# SCH__OldDriver.net
KiCad netlist of a schematic drawn in Altium Designer
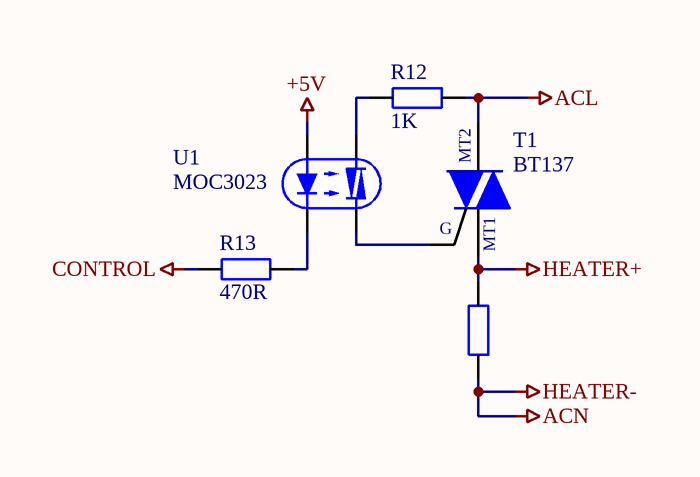
[diagram p0: [SCH]_OldDriver.SchDoc]

(export (version "E")
  (design (tool "Eeschema 10.0.6"))
  (components
    (comp (ref "R12")
      (value "1K")
      (footprint "Res1/4W")
      (description "Resistor 1/4W")
      (libsource (lib "Library") (part "Res 1/4W"))
    )
    (comp (ref "R13")
      (value "470R")
      (footprint "Res1/4W")
      (description "Resistor 1/4W")
      (libsource (lib "Library") (part "Res 1/4W"))
    )
    (comp (ref "SENSOR2")
      (value "5R")
      (footprint "Res1/4W")
      (description "Resistor 1/4W")
      (libsource (lib "Library") (part "Res 1/4W"))
    )
    (comp (ref "T1")
      (value "BT137")
      (footprint "TO220H2")
      (description "Triacs - 8A")
      (libsource (lib "Library") (part "BT137"))
    )
    (comp (ref "U1")
      (value "MOC3023")
      (footprint "DIL6-300b")
      (libsource (lib "Opto Coupler") (part "MOC3023"))
    )
  )
  (nets
    (net (code "1") (name "+5V") (class "Default")
      (node (ref "U1") (pin "1") (pinfunction "A_1") (pintype "passive"))
    )
    (net (code "2") (name "ACL") (class "Default")
      (node (ref "R12") (pin "2") (pinfunction "2_2") (pintype "passive"))
      (node (ref "T1") (pin "2") (pinfunction "MT2_2") (pintype "passive"))
    )
    (net (code "3") (name "ACN") (class "Default")
      (node (ref "SENSOR2") (pin "1") (pinfunction "1_1") (pintype "passive"))
    )
    (net (code "4") (name "CONTROL") (class "Default")
      (node (ref "R13") (pin "1") (pinfunction "1_1") (pintype "passive"))
    )
    (net (code "5") (name "HEATER+") (class "Default")
      (node (ref "SENSOR2") (pin "2") (pinfunction "2_2") (pintype "passive"))
      (node (ref "T1") (pin "1") (pinfunction "MT1_1") (pintype "passive"))
    )
    (net (code "6") (name "Net-(T1-IN)") (class "Default")
      (node (ref "T1") (pin "3") (pinfunction "IN_3") (pintype "passive"))
      (node (ref "U1") (pin "4") (pinfunction "A1_4") (pintype "passive"))
    )
    (net (code "7") (name "Net-(U1-A2)") (class "Default")
      (node (ref "R12") (pin "1") (pinfunction "1_1") (pintype "passive"))
      (node (ref "U1") (pin "6") (pinfunction "A2_6") (pintype "passive"))
    )
    (net (code "8") (name "Net-(U1-C)") (class "Default")
      (node (ref "R13") (pin "2") (pinfunction "2_2") (pintype "passive"))
      (node (ref "U1") (pin "2") (pinfunction "C_2") (pintype "passive"))
    )
  )
)
